# aa8028.net
KiCad netlist of a schematic drawn in Altium Designer
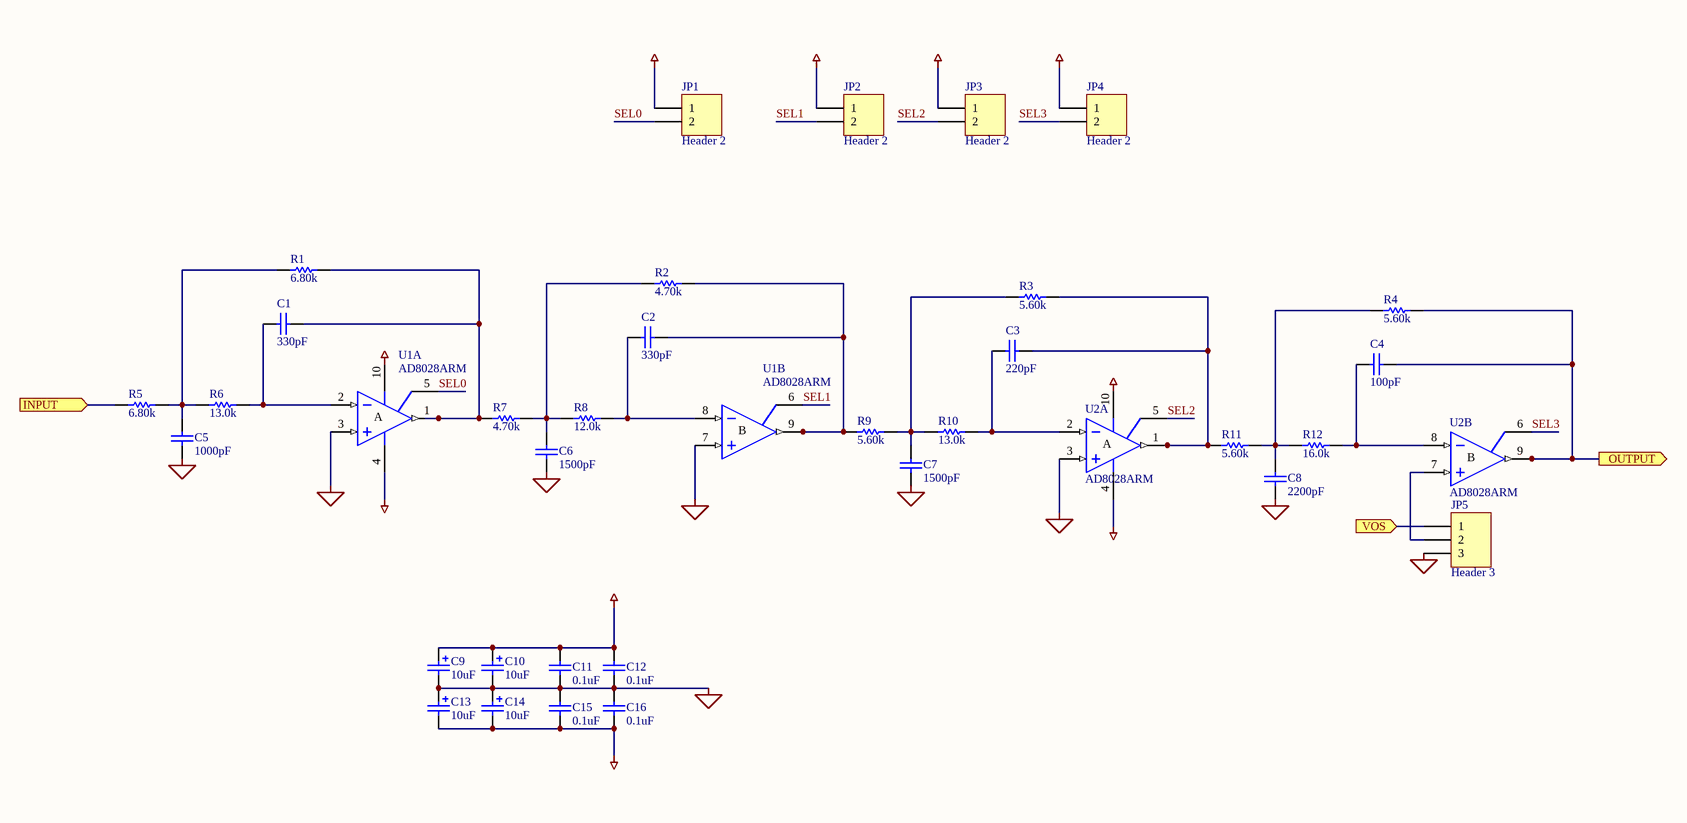
[diagram p0: aa8028.SCHDOC]

(export (version "E")
  (design (tool "Eeschema 10.0.6"))
  (components
    (comp (ref "C1")
      (value "330pF")
      (footprint "0603")
      (description "Capacitor")
      (fields
        (field (name "MANUFACTURER") "Generic Components")
        (field (name "Comment") "Cap")
        (field (name "PUBLISHER") "Altium Limited")
      )
      (libsource (lib "Miscellaneous Devices") (part "Cap"))
    )
    (comp (ref "C2")
      (value "330pF")
      (footprint "0603")
      (description "Capacitor")
      (fields
        (field (name "MANUFACTURER") "Generic Components")
        (field (name "Comment") "Cap")
        (field (name "PUBLISHER") "Altium Limited")
      )
      (libsource (lib "Miscellaneous Devices") (part "Cap"))
    )
    (comp (ref "C3")
      (value "220pF")
      (footprint "0603")
      (description "Capacitor")
      (fields
        (field (name "MANUFACTURER") "Generic Components")
        (field (name "Comment") "Cap")
        (field (name "PUBLISHER") "Altium Limited")
      )
      (libsource (lib "Miscellaneous Devices") (part "Cap"))
    )
    (comp (ref "C4")
      (value "100pF")
      (footprint "0603")
      (description "Capacitor")
      (fields
        (field (name "MANUFACTURER") "Generic Components")
        (field (name "Comment") "Cap")
        (field (name "PUBLISHER") "Altium Limited")
      )
      (libsource (lib "Miscellaneous Devices") (part "Cap"))
    )
    (comp (ref "C5")
      (value "1000pF")
      (footprint "0603")
      (description "Capacitor")
      (fields
        (field (name "MANUFACTURER") "Generic Components")
        (field (name "Comment") "Cap")
        (field (name "PUBLISHER") "Altium Limited")
      )
      (libsource (lib "Miscellaneous Devices") (part "Cap"))
    )
    (comp (ref "C6")
      (value "1500pF")
      (footprint "0603")
      (description "Capacitor")
      (fields
        (field (name "MANUFACTURER") "Generic Components")
        (field (name "Comment") "Cap")
        (field (name "PUBLISHER") "Altium Limited")
      )
      (libsource (lib "Miscellaneous Devices") (part "Cap"))
    )
    (comp (ref "C7")
      (value "1500pF")
      (footprint "0603")
      (description "Capacitor")
      (fields
        (field (name "MANUFACTURER") "Generic Components")
        (field (name "Comment") "Cap")
        (field (name "PUBLISHER") "Altium Limited")
      )
      (libsource (lib "Miscellaneous Devices") (part "Cap"))
    )
    (comp (ref "C8")
      (value "2200pF")
      (footprint "0603")
      (description "Capacitor")
      (fields
        (field (name "MANUFACTURER") "Generic Components")
        (field (name "Comment") "Cap")
        (field (name "PUBLISHER") "Altium Limited")
      )
      (libsource (lib "Miscellaneous Devices") (part "Cap"))
    )
    (comp (ref "C9")
      (value "10uF")
      (footprint "TC3528-1411")
      (description "Polarized Capacitor (Radial)")
      (fields
        (field (name "MANUFACTURER") "Generic Components")
        (field (name "Comment") "Cap Pol1")
        (field (name "PUBLISHER") "Altium Limited")
      )
      (libsource (lib "Miscellaneous Devices") (part "Cap Pol1"))
    )
    (comp (ref "C10")
      (value "10uF")
      (footprint "TC3528-1411")
      (description "Polarized Capacitor (Radial)")
      (fields
        (field (name "MANUFACTURER") "Generic Components")
        (field (name "Comment") "Cap Pol1")
        (field (name "PUBLISHER") "Altium Limited")
      )
      (libsource (lib "Miscellaneous Devices") (part "Cap Pol1"))
    )
    (comp (ref "C11")
      (value "0.1uF")
      (footprint "CC1608-0603")
      (description "Capacitor")
      (fields
        (field (name "MANUFACTURER") "Generic Components")
        (field (name "Comment") "Cap")
        (field (name "PUBLISHER") "Altium Limited")
      )
      (libsource (lib "Miscellaneous Devices") (part "Cap"))
    )
    (comp (ref "C12")
      (value "0.1uF")
      (footprint "CC1608-0603")
      (description "Capacitor")
      (fields
        (field (name "MANUFACTURER") "Generic Components")
        (field (name "Comment") "Cap")
        (field (name "PUBLISHER") "Altium Limited")
      )
      (libsource (lib "Miscellaneous Devices") (part "Cap"))
    )
    (comp (ref "C13")
      (value "10uF")
      (footprint "TC3528-1411")
      (description "Polarized Capacitor (Radial)")
      (fields
        (field (name "MANUFACTURER") "Generic Components")
        (field (name "Comment") "Cap Pol1")
        (field (name "PUBLISHER") "Altium Limited")
      )
      (libsource (lib "Miscellaneous Devices") (part "Cap Pol1"))
    )
    (comp (ref "C14")
      (value "10uF")
      (footprint "TC3528-1411")
      (description "Polarized Capacitor (Radial)")
      (fields
        (field (name "MANUFACTURER") "Generic Components")
        (field (name "Comment") "Cap Pol1")
        (field (name "PUBLISHER") "Altium Limited")
      )
      (libsource (lib "Miscellaneous Devices") (part "Cap Pol1"))
    )
    (comp (ref "C15")
      (value "0.1uF")
      (footprint "CC1608-0603")
      (description "Capacitor")
      (fields
        (field (name "MANUFACTURER") "Generic Components")
        (field (name "Comment") "Cap")
        (field (name "PUBLISHER") "Altium Limited")
      )
      (libsource (lib "Miscellaneous Devices") (part "Cap"))
    )
    (comp (ref "C16")
      (value "0.1uF")
      (footprint "CC1608-0603")
      (description "Capacitor")
      (fields
        (field (name "MANUFACTURER") "Generic Components")
        (field (name "Comment") "Cap")
        (field (name "PUBLISHER") "Altium Limited")
      )
      (libsource (lib "Miscellaneous Devices") (part "Cap"))
    )
    (comp (ref "JP1")
      (value "Header 2")
      (footprint "HDR1X2")
      (description "Header, 2-Pin")
      (fields (field (name "MANUFACTURER") "Generic Components") (field (name "PUBLISHER") "Altium Limited"))
      (libsource (lib "Miscellaneous Connectors") (part "Header 2"))
    )
    (comp (ref "JP2")
      (value "Header 2")
      (footprint "HDR1X2")
      (description "Header, 2-Pin")
      (fields (field (name "MANUFACTURER") "Generic Components") (field (name "PUBLISHER") "Altium Limited"))
      (libsource (lib "Miscellaneous Connectors") (part "Header 2"))
    )
    (comp (ref "JP3")
      (value "Header 2")
      (footprint "HDR1X2")
      (description "Header, 2-Pin")
      (fields (field (name "MANUFACTURER") "Generic Components") (field (name "PUBLISHER") "Altium Limited"))
      (libsource (lib "Miscellaneous Connectors") (part "Header 2"))
    )
    (comp (ref "JP4")
      (value "Header 2")
      (footprint "HDR1X2")
      (description "Header, 2-Pin")
      (fields (field (name "MANUFACTURER") "Generic Components") (field (name "PUBLISHER") "Altium Limited"))
      (libsource (lib "Miscellaneous Connectors") (part "Header 2"))
    )
    (comp (ref "JP5")
      (value "Header 3")
      (footprint "HDR1X3")
      (description "Header, 3-Pin")
      (fields (field (name "MANUFACTURER") "Generic Components") (field (name "PUBLISHER") "Altium Limited"))
      (libsource (lib "Miscellaneous Connectors") (part "Header 3"))
    )
    (comp (ref "R1")
      (value "6.80k")
      (footprint "0603")
      (description "Resistor")
      (fields
        (field (name "MANUFACTURER") "Generic Components")
        (field (name "Comment") "Res1")
        (field (name "PUBLISHER") "Altium Limited")
      )
      (libsource (lib "Miscellaneous Devices") (part "Res1"))
    )
    (comp (ref "R2")
      (value "4.70k")
      (footprint "0603")
      (description "Resistor")
      (fields
        (field (name "MANUFACTURER") "Generic Components")
        (field (name "Comment") "Res1")
        (field (name "PUBLISHER") "Altium Limited")
      )
      (libsource (lib "Miscellaneous Devices") (part "Res1"))
    )
    (comp (ref "R3")
      (value "5.60k")
      (footprint "0603")
      (description "Resistor")
      (fields
        (field (name "MANUFACTURER") "Generic Components")
        (field (name "Comment") "Res1")
        (field (name "PUBLISHER") "Altium Limited")
      )
      (libsource (lib "Miscellaneous Devices") (part "Res1"))
    )
    (comp (ref "R4")
      (value "5.60k")
      (footprint "0603")
      (description "Resistor")
      (fields
        (field (name "MANUFACTURER") "Generic Components")
        (field (name "Comment") "Res1")
        (field (name "PUBLISHER") "Altium Limited")
      )
      (libsource (lib "Miscellaneous Devices") (part "Res1"))
    )
    (comp (ref "R5")
      (value "6.80k")
      (footprint "0603")
      (description "Resistor")
      (fields
        (field (name "MANUFACTURER") "Generic Components")
        (field (name "Comment") "Res1")
        (field (name "PUBLISHER") "Altium Limited")
      )
      (libsource (lib "Miscellaneous Devices") (part "Res1"))
    )
    (comp (ref "R6")
      (value "13.0k")
      (footprint "0603")
      (description "Resistor")
      (fields
        (field (name "MANUFACTURER") "Generic Components")
        (field (name "Comment") "Res1")
        (field (name "PUBLISHER") "Altium Limited")
      )
      (libsource (lib "Miscellaneous Devices") (part "Res1"))
    )
    (comp (ref "R7")
      (value "4.70k")
      (footprint "0603")
      (description "Resistor")
      (fields
        (field (name "MANUFACTURER") "Generic Components")
        (field (name "Comment") "Res1")
        (field (name "PUBLISHER") "Altium Limited")
      )
      (libsource (lib "Miscellaneous Devices") (part "Res1"))
    )
    (comp (ref "R8")
      (value "12.0k")
      (footprint "0603")
      (description "Resistor")
      (fields
        (field (name "MANUFACTURER") "Generic Components")
        (field (name "Comment") "Res1")
        (field (name "PUBLISHER") "Altium Limited")
      )
      (libsource (lib "Miscellaneous Devices") (part "Res1"))
    )
    (comp (ref "R9")
      (value "5.60k")
      (footprint "0603")
      (description "Resistor")
      (fields
        (field (name "MANUFACTURER") "Generic Components")
        (field (name "Comment") "Res1")
        (field (name "PUBLISHER") "Altium Limited")
      )
      (libsource (lib "Miscellaneous Devices") (part "Res1"))
    )
    (comp (ref "R10")
      (value "13.0k")
      (footprint "0603")
      (description "Resistor")
      (fields
        (field (name "MANUFACTURER") "Generic Components")
        (field (name "Comment") "Res1")
        (field (name "PUBLISHER") "Altium Limited")
      )
      (libsource (lib "Miscellaneous Devices") (part "Res1"))
    )
    (comp (ref "R11")
      (value "5.60k")
      (footprint "0603")
      (description "Resistor")
      (fields
        (field (name "MANUFACTURER") "Generic Components")
        (field (name "Comment") "Res1")
        (field (name "PUBLISHER") "Altium Limited")
      )
      (libsource (lib "Miscellaneous Devices") (part "Res1"))
    )
    (comp (ref "R12")
      (value "16.0k")
      (footprint "0603")
      (description "Resistor")
      (fields
        (field (name "MANUFACTURER") "Generic Components")
        (field (name "Comment") "Res1")
        (field (name "PUBLISHER") "Altium Limited")
      )
      (libsource (lib "Miscellaneous Devices") (part "Res1"))
    )
    (comp (ref "U1")
      (value "AD8028ARM")
      (footprint "TSSO3x5-G10")
      (description "Analog Devices Low Distortion, High Speed RRIO OA")
      (libsource (lib "My devices") (part "AD8028ARM"))
    )
    (comp (ref "U2")
      (value "AD8028ARM")
      (footprint "TSSO3x5-G10")
      (description "Analog Devices Low Distortion, High Speed RRIO OA")
      (libsource (lib "My devices") (part "AD8028ARM"))
    )
  )
  (nets
    (net (code "1") (name "/INPUT") (class "Default")
      (node (ref "R5") (pin "1") (pinfunction "1_1") (pintype "passive"))
    )
    (net (code "2") (name "/OUTPUT") (class "Default")
      (node (ref "C4") (pin "1") (pinfunction "1_1") (pintype "passive"))
      (node (ref "R4") (pin "1") (pinfunction "1_1") (pintype "passive"))
      (node (ref "U2") (pin "9") (pinfunction "VOUTB_9") (pintype "output"))
    )
    (net (code "3") (name "/SEL0") (class "Default")
      (node (ref "JP1") (pin "2") (pinfunction "2_2") (pintype "passive"))
      (node (ref "U1") (pin "5") (pinfunction "SELA_5") (pintype "passive"))
    )
    (net (code "4") (name "/SEL1") (class "Default")
      (node (ref "JP2") (pin "2") (pinfunction "2_2") (pintype "passive"))
      (node (ref "U1") (pin "6") (pinfunction "SELB_6") (pintype "passive"))
    )
    (net (code "5") (name "/SEL2") (class "Default")
      (node (ref "JP3") (pin "2") (pinfunction "2_2") (pintype "passive"))
      (node (ref "U2") (pin "5") (pinfunction "SELA_5") (pintype "passive"))
    )
    (net (code "6") (name "/SEL3") (class "Default")
      (node (ref "JP4") (pin "2") (pinfunction "2_2") (pintype "passive"))
      (node (ref "U2") (pin "6") (pinfunction "SELB_6") (pintype "passive"))
    )
    (net (code "7") (name "/VOS") (class "Default")
      (node (ref "JP5") (pin "1") (pinfunction "1_1") (pintype "passive"))
    )
    (net (code "8") (name "AGND") (class "Default")
      (node (ref "C10") (pin "2") (pinfunction "2_2") (pintype "passive"))
      (node (ref "C11") (pin "1") (pinfunction "1_1") (pintype "passive"))
      (node (ref "C12") (pin "1") (pinfunction "1_1") (pintype "passive"))
      (node (ref "C13") (pin "1") (pinfunction "1_1") (pintype "passive"))
      (node (ref "C14") (pin "1") (pinfunction "1_1") (pintype "passive"))
      (node (ref "C15") (pin "2") (pinfunction "2_2") (pintype "passive"))
      (node (ref "C16") (pin "2") (pinfunction "2_2") (pintype "passive"))
      (node (ref "C5") (pin "1") (pinfunction "1_1") (pintype "passive"))
      (node (ref "C6") (pin "1") (pinfunction "1_1") (pintype "passive"))
      (node (ref "C7") (pin "1") (pinfunction "1_1") (pintype "passive"))
      (node (ref "C8") (pin "1") (pinfunction "1_1") (pintype "passive"))
      (node (ref "C9") (pin "2") (pinfunction "2_2") (pintype "passive"))
      (node (ref "JP5") (pin "3") (pinfunction "3_3") (pintype "passive"))
      (node (ref "U1") (pin "3") (pinfunction "IN+A_3") (pintype "input"))
      (node (ref "U1") (pin "7") (pinfunction "IN+B_7") (pintype "input"))
      (node (ref "U2") (pin "3") (pinfunction "IN+A_3") (pintype "input"))
    )
    (net (code "9") (name "AVDD") (class "Default")
      (node (ref "C10") (pin "1") (pinfunction "1_1") (pintype "passive"))
      (node (ref "C11") (pin "2") (pinfunction "2_2") (pintype "passive"))
      (node (ref "C12") (pin "2") (pinfunction "2_2") (pintype "passive"))
      (node (ref "C9") (pin "1") (pinfunction "1_1") (pintype "passive"))
      (node (ref "JP1") (pin "1") (pinfunction "1_1") (pintype "passive"))
      (node (ref "JP2") (pin "1") (pinfunction "1_1") (pintype "passive"))
      (node (ref "JP3") (pin "1") (pinfunction "1_1") (pintype "passive"))
      (node (ref "JP4") (pin "1") (pinfunction "1_1") (pintype "passive"))
      (node (ref "U1") (pin "10") (pinfunction "V+_10") (pintype "power_in"))
      (node (ref "U2") (pin "10") (pinfunction "V+_10") (pintype "power_in"))
    )
    (net (code "10") (name "AVSS") (class "Default")
      (node (ref "C13") (pin "2") (pinfunction "2_2") (pintype "passive"))
      (node (ref "C14") (pin "2") (pinfunction "2_2") (pintype "passive"))
      (node (ref "C15") (pin "1") (pinfunction "1_1") (pintype "passive"))
      (node (ref "C16") (pin "1") (pinfunction "1_1") (pintype "passive"))
      (node (ref "U1") (pin "4") (pinfunction "V-_4") (pintype "power_in"))
      (node (ref "U2") (pin "4") (pinfunction "V-_4") (pintype "power_in"))
    )
    (net (code "11") (name "Net-(C5-Pad2)") (class "Default")
      (node (ref "C5") (pin "2") (pinfunction "2_2") (pintype "passive"))
      (node (ref "R1") (pin "2") (pinfunction "2_2") (pintype "passive"))
      (node (ref "R5") (pin "2") (pinfunction "2_2") (pintype "passive"))
      (node (ref "R6") (pin "1") (pinfunction "1_1") (pintype "passive"))
    )
    (net (code "12") (name "Net-(C6-Pad2)") (class "Default")
      (node (ref "C6") (pin "2") (pinfunction "2_2") (pintype "passive"))
      (node (ref "R2") (pin "2") (pinfunction "2_2") (pintype "passive"))
      (node (ref "R7") (pin "2") (pinfunction "2_2") (pintype "passive"))
      (node (ref "R8") (pin "1") (pinfunction "1_1") (pintype "passive"))
    )
    (net (code "13") (name "Net-(C7-Pad2)") (class "Default")
      (node (ref "C7") (pin "2") (pinfunction "2_2") (pintype "passive"))
      (node (ref "R10") (pin "1") (pinfunction "1_1") (pintype "passive"))
      (node (ref "R3") (pin "2") (pinfunction "2_2") (pintype "passive"))
      (node (ref "R9") (pin "2") (pinfunction "2_2") (pintype "passive"))
    )
    (net (code "14") (name "Net-(C8-Pad2)") (class "Default")
      (node (ref "C8") (pin "2") (pinfunction "2_2") (pintype "passive"))
      (node (ref "R11") (pin "2") (pinfunction "2_2") (pintype "passive"))
      (node (ref "R12") (pin "1") (pinfunction "1_1") (pintype "passive"))
      (node (ref "R4") (pin "2") (pinfunction "2_2") (pintype "passive"))
    )
    (net (code "15") (name "Net-(U1A-IN-A)") (class "Default")
      (node (ref "C1") (pin "2") (pinfunction "2_2") (pintype "passive"))
      (node (ref "R6") (pin "2") (pinfunction "2_2") (pintype "passive"))
      (node (ref "U1") (pin "2") (pinfunction "IN-A_2") (pintype "input"))
    )
    (net (code "16") (name "Net-(U1A-VOUTA)") (class "Default")
      (node (ref "C1") (pin "1") (pinfunction "1_1") (pintype "passive"))
      (node (ref "R1") (pin "1") (pinfunction "1_1") (pintype "passive"))
      (node (ref "R7") (pin "1") (pinfunction "1_1") (pintype "passive"))
      (node (ref "U1") (pin "1") (pinfunction "VOUTA_1") (pintype "output"))
    )
    (net (code "17") (name "Net-(U1B-IN-B)") (class "Default")
      (node (ref "C2") (pin "2") (pinfunction "2_2") (pintype "passive"))
      (node (ref "R8") (pin "2") (pinfunction "2_2") (pintype "passive"))
      (node (ref "U1") (pin "8") (pinfunction "IN-B_8") (pintype "input"))
    )
    (net (code "18") (name "Net-(U1B-VOUTB)") (class "Default")
      (node (ref "C2") (pin "1") (pinfunction "1_1") (pintype "passive"))
      (node (ref "R2") (pin "1") (pinfunction "1_1") (pintype "passive"))
      (node (ref "R9") (pin "1") (pinfunction "1_1") (pintype "passive"))
      (node (ref "U1") (pin "9") (pinfunction "VOUTB_9") (pintype "output"))
    )
    (net (code "19") (name "Net-(U2A-IN-A)") (class "Default")
      (node (ref "C3") (pin "2") (pinfunction "2_2") (pintype "passive"))
      (node (ref "R10") (pin "2") (pinfunction "2_2") (pintype "passive"))
      (node (ref "U2") (pin "2") (pinfunction "IN-A_2") (pintype "input"))
    )
    (net (code "20") (name "Net-(U2A-VOUTA)") (class "Default")
      (node (ref "C3") (pin "1") (pinfunction "1_1") (pintype "passive"))
      (node (ref "R11") (pin "1") (pinfunction "1_1") (pintype "passive"))
      (node (ref "R3") (pin "1") (pinfunction "1_1") (pintype "passive"))
      (node (ref "U2") (pin "1") (pinfunction "VOUTA_1") (pintype "output"))
    )
    (net (code "21") (name "Net-(U2B-IN+B)") (class "Default")
      (node (ref "JP5") (pin "2") (pinfunction "2_2") (pintype "passive"))
      (node (ref "U2") (pin "7") (pinfunction "IN+B_7") (pintype "input"))
    )
    (net (code "22") (name "Net-(U2B-IN-B)") (class "Default")
      (node (ref "C4") (pin "2") (pinfunction "2_2") (pintype "passive"))
      (node (ref "R12") (pin "2") (pinfunction "2_2") (pintype "passive"))
      (node (ref "U2") (pin "8") (pinfunction "IN-B_8") (pintype "input"))
    )
  )
)
